# arduino_Uno_RevG-MU.net
KiCad netlist of a schematic drawn in EAGLE
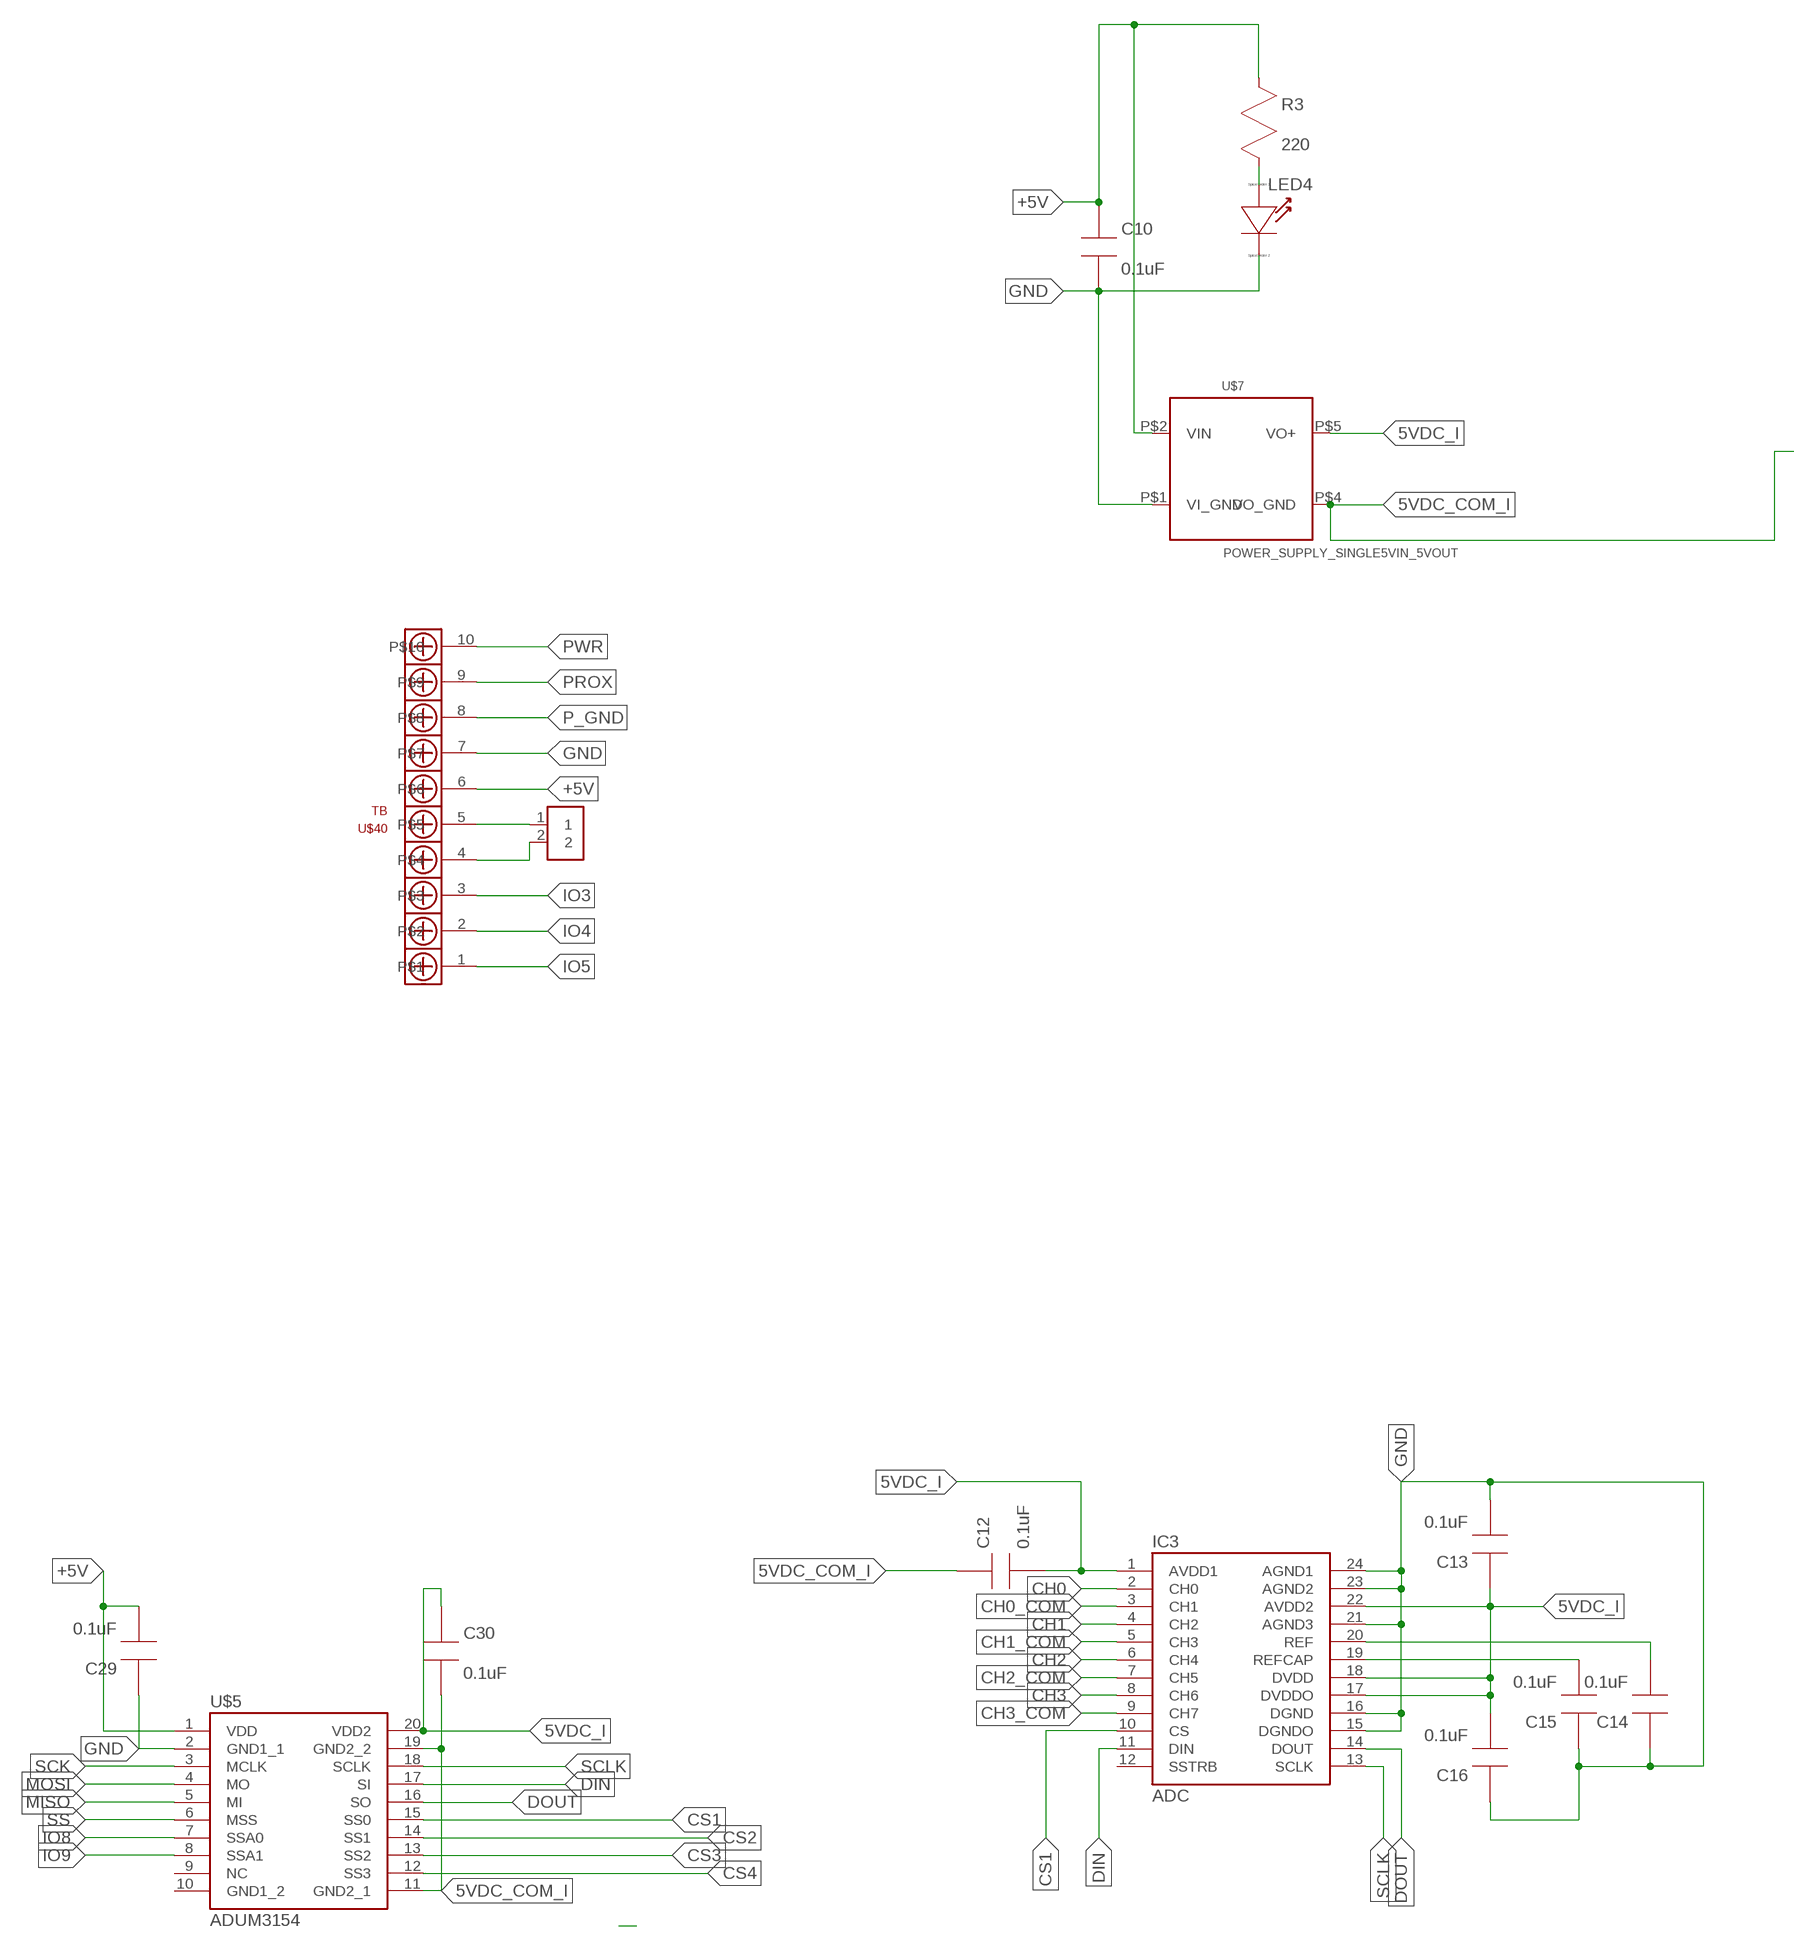
[diagram p0: schematic, sheet 1, part 1 of 2]
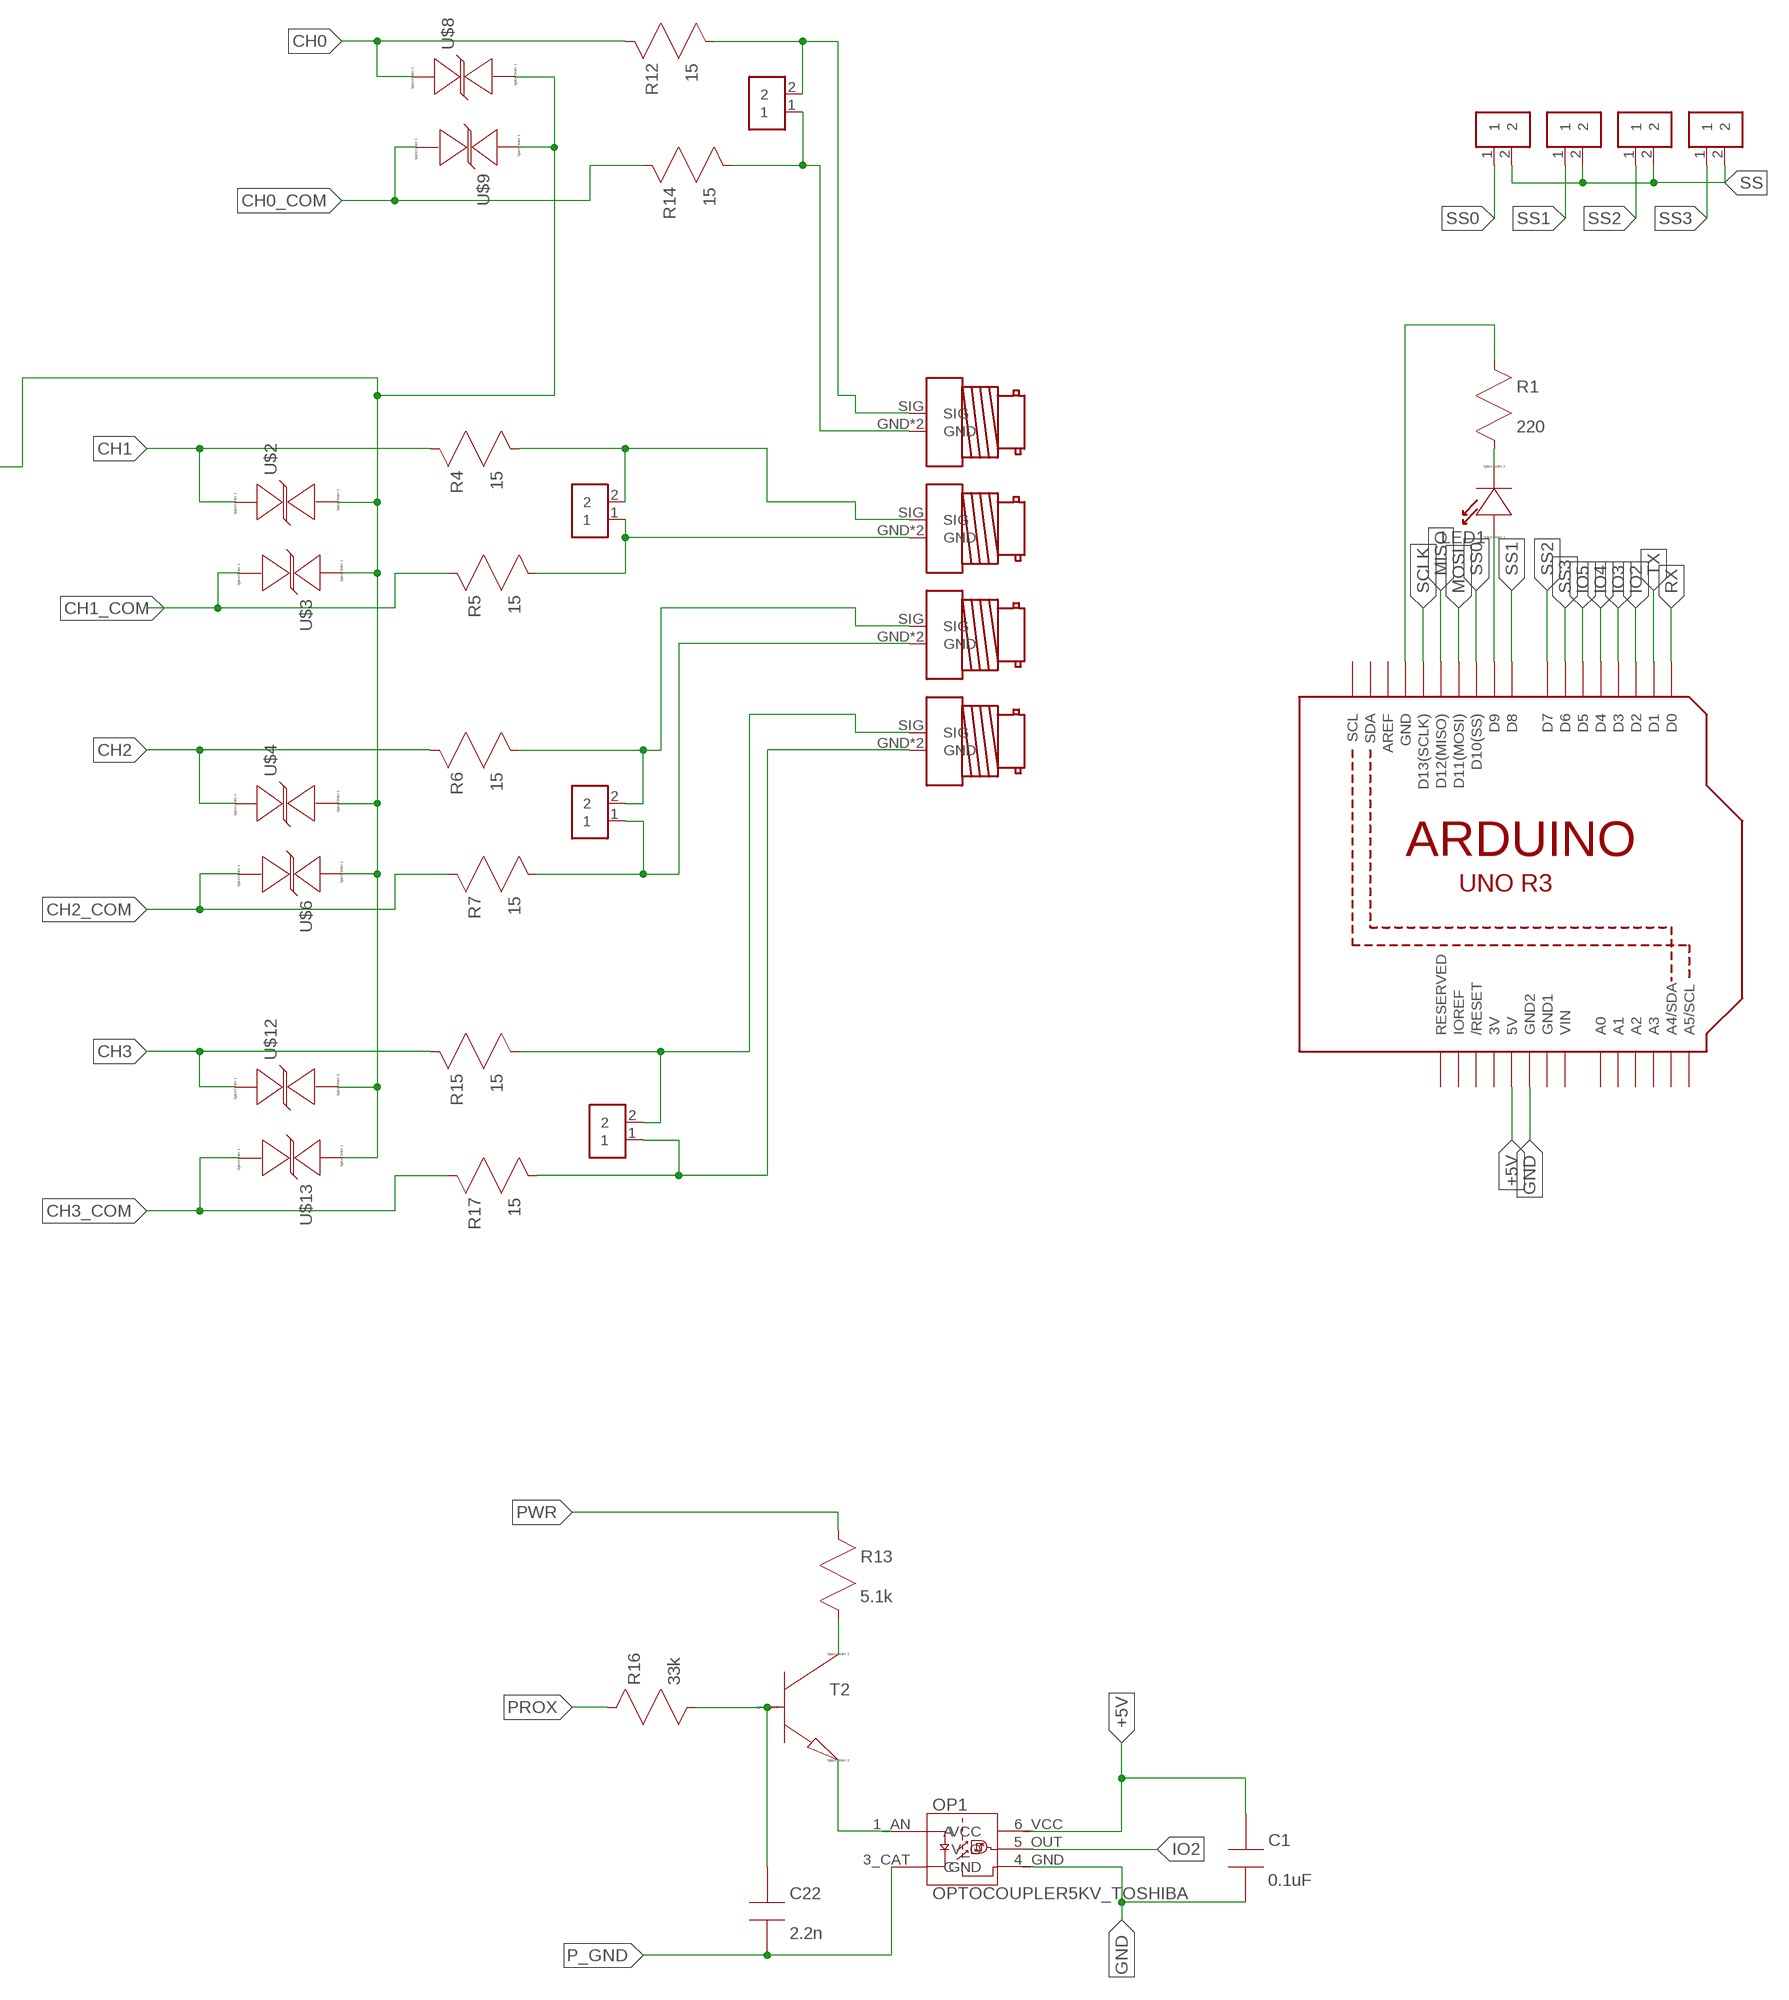
[diagram p1: schematic, sheet 1, part 2 of 2]

(export (version "E")
  (design (tool "Eeschema 10.0.6"))
  (components
    (comp (ref "C1")
      (value "0.1uF")
      (footprint "eagle-import:0805_SMD")
      (fields (field (name "MPN") "C0805C104M5UACTU"))
      (libsource (lib "eagle-import") (part "CAPACITOR0.1U_50V"))
    )
    (comp (ref "C10")
      (value "0.1uF")
      (footprint "eagle-import:0805_SMD")
      (fields (field (name "MPN") "C0805C104M5UACTU"))
      (libsource (lib "eagle-import") (part "CAPACITOR0.1U_50V"))
    )
    (comp (ref "C12")
      (value "0.1uF")
      (footprint "eagle-import:0805_SMD")
      (fields (field (name "MPN") "C0805C104M5UACTU"))
      (libsource (lib "eagle-import") (part "CAPACITOR0.1U_50V"))
    )
    (comp (ref "C13")
      (value "0.1uF")
      (footprint "eagle-import:0805_SMD")
      (fields (field (name "MPN") "C0805C104M5UACTU"))
      (libsource (lib "eagle-import") (part "CAPACITOR0.1U_50V"))
    )
    (comp (ref "C14")
      (value "0.1uF")
      (footprint "eagle-import:0805_SMD")
      (fields (field (name "MPN") "C0805C104M5UACTU"))
      (libsource (lib "eagle-import") (part "CAPACITOR0.1U_50V"))
    )
    (comp (ref "C15")
      (value "0.1uF")
      (footprint "eagle-import:0805_SMD")
      (fields (field (name "MPN") "C0805C104M5UACTU"))
      (libsource (lib "eagle-import") (part "CAPACITOR0.1U_50V"))
    )
    (comp (ref "C16")
      (value "0.1uF")
      (footprint "eagle-import:0805_SMD")
      (fields (field (name "MPN") "C0805C104M5UACTU"))
      (libsource (lib "eagle-import") (part "CAPACITOR0.1U_50V"))
    )
    (comp (ref "C22")
      (value "2.2n")
      (footprint "eagle-import:0805_SMD")
      (fields (field (name "MPN") "C0805C222K5RACTU"))
      (libsource (lib "eagle-import") (part "CAPACITOR2.2N_0805"))
    )
    (comp (ref "C29")
      (value "0.1uF")
      (footprint "eagle-import:0805_SMD")
      (fields (field (name "MPN") "C0805C104M5UACTU"))
      (libsource (lib "eagle-import") (part "CAPACITOR0.1U_50V"))
    )
    (comp (ref "C30")
      (value "0.1uF")
      (footprint "eagle-import:0805_SMD")
      (fields (field (name "MPN") "C0805C104M5UACTU"))
      (libsource (lib "eagle-import") (part "CAPACITOR0.1U_50V"))
    )
    (comp (ref "IC3")
      (value "ADC")
      (footprint "eagle-import:LS_ELECTRIC_HTSSOP24-PAD")
      (fields (field (name "MPN") "MAX1300AEUG+"))
      (libsource (lib "eagle-import") (part "ADC"))
    )
    (comp (ref "LED1")
      (value "LED0805_GREEN")
      (footprint "eagle-import:LED_0805")
      (fields (field (name "MPN") "LTST-C171GKT"))
      (libsource (lib "eagle-import") (part "LED0805_GREEN"))
    )
    (comp (ref "LED4")
      (value "LED0805_GREEN")
      (footprint "eagle-import:LED_0805")
      (fields (field (name "MPN") "LTST-C171GKT"))
      (libsource (lib "eagle-import") (part "LED0805_GREEN"))
    )
    (comp (ref "OP1")
      (value "OPTOCOUPLER5KV_TOSHIBA")
      (footprint "eagle-import:SO6L")
      (fields (field (name "MPN") "TLP2745(TP,E"))
      (libsource (lib "eagle-import") (part "OPTOCOUPLER5KV_TOSHIBA"))
    )
    (comp (ref "R1")
      (value "220")
      (footprint "eagle-import:0805_SMD")
      (fields (field (name "MPN") "RC0805FR-07220RL"))
      (libsource (lib "eagle-import") (part "RESISTOR220_0805"))
    )
    (comp (ref "R3")
      (value "220")
      (footprint "eagle-import:0805_SMD")
      (fields (field (name "MPN") "RC0805FR-07220RL"))
      (libsource (lib "eagle-import") (part "RESISTOR220_0805"))
    )
    (comp (ref "R4")
      (value "15")
      (footprint "eagle-import:0805_SMD")
      (fields (field (name "MPN") "RC0805FR-0715RL"))
      (libsource (lib "eagle-import") (part "RESISTOR15_0805"))
    )
    (comp (ref "R5")
      (value "15")
      (footprint "eagle-import:0805_SMD")
      (fields (field (name "MPN") "RC0805FR-0715RL"))
      (libsource (lib "eagle-import") (part "RESISTOR15_0805"))
    )
    (comp (ref "R6")
      (value "15")
      (footprint "eagle-import:0805_SMD")
      (fields (field (name "MPN") "RC0805FR-0715RL"))
      (libsource (lib "eagle-import") (part "RESISTOR15_0805"))
    )
    (comp (ref "R7")
      (value "15")
      (footprint "eagle-import:0805_SMD")
      (fields (field (name "MPN") "RC0805FR-0715RL"))
      (libsource (lib "eagle-import") (part "RESISTOR15_0805"))
    )
    (comp (ref "R12")
      (value "15")
      (footprint "eagle-import:0805_SMD")
      (fields (field (name "MPN") "RC0805FR-0715RL"))
      (libsource (lib "eagle-import") (part "RESISTOR15_0805"))
    )
    (comp (ref "R13")
      (value "5.1k")
      (footprint "eagle-import:0805_SMD")
      (fields (field (name "MPN") "RC0805FR-075K1L"))
      (libsource (lib "eagle-import") (part "RESISTOR5.1K_0805"))
    )
    (comp (ref "R14")
      (value "15")
      (footprint "eagle-import:0805_SMD")
      (fields (field (name "MPN") "RC0805FR-0715RL"))
      (libsource (lib "eagle-import") (part "RESISTOR15_0805"))
    )
    (comp (ref "R15")
      (value "15")
      (footprint "eagle-import:0805_SMD")
      (fields (field (name "MPN") "RC0805FR-0715RL"))
      (libsource (lib "eagle-import") (part "RESISTOR15_0805"))
    )
    (comp (ref "R16")
      (value "33k")
      (footprint "eagle-import:0805_SMD")
      (fields (field (name "MPN") "RC0805FR-0733KL"))
      (libsource (lib "eagle-import") (part "RESISTOR33K_0805"))
    )
    (comp (ref "R17")
      (value "15")
      (footprint "eagle-import:0805_SMD")
      (fields (field (name "MPN") "RC0805FR-0715RL"))
      (libsource (lib "eagle-import") (part "RESISTOR15_0805"))
    )
    (comp (ref "T2")
      (value "TRANSISTOR_NPNMMBT3904L")
      (footprint "eagle-import:SOT23")
      (fields (field (name "MPN") "MMBT3904LT1G"))
      (libsource (lib "eagle-import") (part "TRANSISTOR_NPNMMBT3904L"))
    )
    (comp (ref "U$1")
      (value "CH2")
      (footprint "eagle-import:BNC")
      (fields (field (name "MPN") "031-5431-10RFX"))
      (libsource (lib "eagle-import") (part "BNC_INVBNC_INVERT"))
    )
    (comp (ref "U$2")
      (value "TSV14VAC_18VDC")
      (footprint "eagle-import:0805_SMD")
      (fields (field (name "MPN") "VCAS08LC18A500DP"))
      (libsource (lib "eagle-import") (part "TSV14VAC_18VDC"))
    )
    (comp (ref "U$3")
      (value "TSV14VAC_18VDC")
      (footprint "eagle-import:0805_SMD")
      (fields (field (name "MPN") "VCAS08LC18A500DP"))
      (libsource (lib "eagle-import") (part "TSV14VAC_18VDC"))
    )
    (comp (ref "U$4")
      (value "TSV14VAC_18VDC")
      (footprint "eagle-import:0805_SMD")
      (fields (field (name "MPN") "VCAS08LC18A500DP"))
      (libsource (lib "eagle-import") (part "TSV14VAC_18VDC"))
    )
    (comp (ref "U$5")
      (value "ADUM3154")
      (footprint "eagle-import:SSOP_20")
      (fields (field (name "MPN") "ADUM3154ARSZ-RL7"))
      (libsource (lib "eagle-import") (part "ADUM3154"))
    )
    (comp (ref "U$6")
      (value "TSV14VAC_18VDC")
      (footprint "eagle-import:0805_SMD")
      (fields (field (name "MPN") "VCAS08LC18A500DP"))
      (libsource (lib "eagle-import") (part "TSV14VAC_18VDC"))
    )
    (comp (ref "U$7")
      (value "POWER_SUPPLY_SINGLE5VIN_5VOUT")
      (footprint "eagle-import:SMT-R1SE-0505")
      (fields (field (name "MPN") "R1SE-0505-R"))
      (libsource (lib "eagle-import") (part "POWER_SUPPLY_SINGLE5VIN_5VOUT"))
    )
    (comp (ref "U$8")
      (value "TSV14VAC_18VDC")
      (footprint "eagle-import:0805_SMD")
      (fields (field (name "MPN") "VCAS08LC18A500DP"))
      (libsource (lib "eagle-import") (part "TSV14VAC_18VDC"))
    )
    (comp (ref "U$9")
      (value "TSV14VAC_18VDC")
      (footprint "eagle-import:0805_SMD")
      (fields (field (name "MPN") "VCAS08LC18A500DP"))
      (libsource (lib "eagle-import") (part "TSV14VAC_18VDC"))
    )
    (comp (ref "U$10")
      (value "1X2_HEADER1X2")
      (footprint "eagle-import:1X2_HEADER")
      (fields (field (name "MPN") "0022032021"))
      (libsource (lib "eagle-import") (part "1X2_HEADER1X2"))
    )
    (comp (ref "U$11")
      (value "1X2_HEADER1X2")
      (footprint "eagle-import:1X2_HEADER")
      (fields (field (name "MPN") "0022032021"))
      (libsource (lib "eagle-import") (part "1X2_HEADER1X2"))
    )
    (comp (ref "U$12")
      (value "TSV14VAC_18VDC")
      (footprint "eagle-import:0805_SMD")
      (fields (field (name "MPN") "VCAS08LC18A500DP"))
      (libsource (lib "eagle-import") (part "TSV14VAC_18VDC"))
    )
    (comp (ref "U$13")
      (value "TSV14VAC_18VDC")
      (footprint "eagle-import:0805_SMD")
      (fields (field (name "MPN") "VCAS08LC18A500DP"))
      (libsource (lib "eagle-import") (part "TSV14VAC_18VDC"))
    )
    (comp (ref "U$14")
      (value "1X2_HEADER1X2")
      (footprint "eagle-import:1X2_HEADER")
      (fields (field (name "MPN") "0022032021"))
      (libsource (lib "eagle-import") (part "1X2_HEADER1X2"))
    )
    (comp (ref "U$15")
      (value "1X2_HEADER1X2")
      (footprint "eagle-import:1X2_HEADER")
      (fields (field (name "MPN") "0022032021"))
      (libsource (lib "eagle-import") (part "1X2_HEADER1X2"))
    )
    (comp (ref "U$16")
      (value "1X2_HEADER1X2")
      (footprint "eagle-import:1X2_HEADER")
      (fields (field (name "MPN") "0022032021"))
      (libsource (lib "eagle-import") (part "1X2_HEADER1X2"))
    )
    (comp (ref "U$17")
      (value "1X2_HEADER1X2")
      (footprint "eagle-import:1X2_HEADER")
      (fields (field (name "MPN") "0022032021"))
      (libsource (lib "eagle-import") (part "1X2_HEADER1X2"))
    )
    (comp (ref "U$18")
      (value "1X2_HEADER1X2")
      (footprint "eagle-import:1X2_HEADER")
      (fields (field (name "MPN") "0022032021"))
      (libsource (lib "eagle-import") (part "1X2_HEADER1X2"))
    )
    (comp (ref "U$19")
      (value "1X2_HEADER1X2")
      (footprint "eagle-import:1X2_HEADER")
      (fields (field (name "MPN") "0022032021"))
      (libsource (lib "eagle-import") (part "1X2_HEADER1X2"))
    )
    (comp (ref "U$20")
      (value "1X2_HEADER1X2")
      (footprint "eagle-import:1X2_HEADER")
      (fields (field (name "MPN") "0022032021"))
      (libsource (lib "eagle-import") (part "1X2_HEADER1X2"))
    )
    (comp (ref "U$34")
      (value "CH1")
      (footprint "eagle-import:BNC")
      (fields (field (name "MPN") "031-5431-10RFX"))
      (libsource (lib "eagle-import") (part "BNC_INVBNC_INVERT"))
    )
    (comp (ref "U$35")
      (value "CH3")
      (footprint "eagle-import:BNC")
      (fields (field (name "MPN") "031-5431-10RFX"))
      (libsource (lib "eagle-import") (part "BNC_INVBNC_INVERT"))
    )
    (comp (ref "U$36")
      (value "CG4")
      (footprint "eagle-import:BNC")
      (fields (field (name "MPN") "031-5431-10RFX"))
      (libsource (lib "eagle-import") (part "BNC_INVBNC_INVERT"))
    )
    (comp (ref "U$40")
      (value "TB")
      (footprint "eagle-import:TB_10P")
      (libsource (lib "eagle-import") (part "TERMINAL_BLOCK_10PHOENIX_10"))
    )
    (comp (ref "U4")
      (value "ARDUINOR3-DIMENSION")
      (footprint "eagle-import:ARDUINOR3")
      (libsource (lib "eagle-import") (part "ARDUINOR3-DIMENSION"))
    )
  )
  (nets
    (net (code "1") (name "+5V") (class "Default")
      (node (ref "C1") (pin "1") (pinfunction "A_1") (pintype "passive"))
      (node (ref "C10") (pin "1") (pinfunction "A_1") (pintype "passive"))
      (node (ref "C29") (pin "2") (pinfunction "B_2") (pintype "passive"))
      (node (ref "OP1") (pin "6_VCC") (pinfunction "VCC_6_VCC") (pintype "bidirectional"))
      (node (ref "R3") (pin "1") (pinfunction "A_1") (pintype "passive"))
      (node (ref "U$40") (pin "6") (pinfunction "P$6_6") (pintype "bidirectional"))
      (node (ref "U$5") (pin "1") (pinfunction "VDD_1") (pintype "power_in"))
      (node (ref "U$7") (pin "P$2") (pinfunction "VIN_P$2") (pintype "bidirectional"))
      (node (ref "U4") (pin "5V") (pinfunction "5V_5V") (pintype "power_in"))
    )
    (net (code "2") (name "/3V") (class "Default")
      (node (ref "U4") (pin "3V") (pinfunction "3V_3V") (pintype "power_in"))
    )
    (net (code "3") (name "/GND1") (class "Default")
      (node (ref "U4") (pin "GND1") (pinfunction "GND1_GND1") (pintype "power_in"))
    )
    (net (code "4") (name "/SSTRB") (class "Default")
      (node (ref "IC3") (pin "12") (pinfunction "SSTRB_12") (pintype "power_in"))
    )
    (net (code "5") (name "/VIN") (class "Default")
      (node (ref "U4") (pin "VIN") (pinfunction "VIN_VIN") (pintype "power_in"))
    )
    (net (code "6") (name "5VDC_COM_I") (class "Default")
      (node (ref "C12") (pin "1") (pinfunction "A_1") (pintype "passive"))
      (node (ref "C30") (pin "2") (pinfunction "B_2") (pintype "passive"))
      (node (ref "U$12") (pin "2") (pinfunction "GND_2") (pintype "passive"))
      (node (ref "U$13") (pin "1") (pinfunction "+_1") (pintype "passive"))
      (node (ref "U$2") (pin "2") (pinfunction "GND_2") (pintype "passive"))
      (node (ref "U$3") (pin "1") (pinfunction "+_1") (pintype "passive"))
      (node (ref "U$4") (pin "2") (pinfunction "GND_2") (pintype "passive"))
      (node (ref "U$5") (pin "11") (pinfunction "GND2_1_11") (pintype "bidirectional"))
      (node (ref "U$5") (pin "19") (pinfunction "GND2_2_19") (pintype "bidirectional"))
      (node (ref "U$6") (pin "1") (pinfunction "+_1") (pintype "passive"))
      (node (ref "U$7") (pin "P$4") (pinfunction "VO_GND_P$4") (pintype "bidirectional"))
      (node (ref "U$8") (pin "2") (pinfunction "GND_2") (pintype "passive"))
      (node (ref "U$9") (pin "1") (pinfunction "+_1") (pintype "passive"))
    )
    (net (code "7") (name "5VDC_I") (class "Default")
      (node (ref "C12") (pin "2") (pinfunction "B_2") (pintype "passive"))
      (node (ref "C13") (pin "1") (pinfunction "A_1") (pintype "passive"))
      (node (ref "C16") (pin "2") (pinfunction "B_2") (pintype "passive"))
      (node (ref "C30") (pin "1") (pinfunction "A_1") (pintype "passive"))
      (node (ref "IC3") (pin "1") (pinfunction "AVDD1_1") (pintype "power_in"))
      (node (ref "IC3") (pin "17") (pinfunction "DVDDO_17") (pintype "bidirectional"))
      (node (ref "IC3") (pin "18") (pinfunction "DVDD_18") (pintype "bidirectional"))
      (node (ref "IC3") (pin "22") (pinfunction "AVDD2_22") (pintype "bidirectional"))
      (node (ref "U$5") (pin "20") (pinfunction "VDD2_20") (pintype "bidirectional"))
      (node (ref "U$7") (pin "P$5") (pinfunction "VO+_P$5") (pintype "bidirectional"))
    )
    (net (code "8") (name "CH0") (class "Default")
      (node (ref "IC3") (pin "2") (pinfunction "CH0_2") (pintype "power_in"))
      (node (ref "R12") (pin "1") (pinfunction "A_1") (pintype "passive"))
      (node (ref "U$8") (pin "1") (pinfunction "+_1") (pintype "passive"))
    )
    (net (code "9") (name "CH0_COM") (class "Default")
      (node (ref "IC3") (pin "3") (pinfunction "CH1_3") (pintype "bidirectional"))
      (node (ref "R14") (pin "1") (pinfunction "A_1") (pintype "passive"))
      (node (ref "U$9") (pin "2") (pinfunction "GND_2") (pintype "passive"))
    )
    (net (code "10") (name "CH1") (class "Default")
      (node (ref "IC3") (pin "4") (pinfunction "CH2_4") (pintype "power_in"))
      (node (ref "R4") (pin "1") (pinfunction "A_1") (pintype "passive"))
      (node (ref "U$2") (pin "1") (pinfunction "+_1") (pintype "passive"))
    )
    (net (code "11") (name "CH1_COM") (class "Default")
      (node (ref "IC3") (pin "5") (pinfunction "CH3_5") (pintype "bidirectional"))
      (node (ref "R5") (pin "1") (pinfunction "A_1") (pintype "passive"))
      (node (ref "U$3") (pin "2") (pinfunction "GND_2") (pintype "passive"))
    )
    (net (code "12") (name "CH2") (class "Default")
      (node (ref "IC3") (pin "6") (pinfunction "CH4_6") (pintype "bidirectional"))
      (node (ref "R6") (pin "1") (pinfunction "A_1") (pintype "passive"))
      (node (ref "U$4") (pin "1") (pinfunction "+_1") (pintype "passive"))
    )
    (net (code "13") (name "CH2_COM") (class "Default")
      (node (ref "IC3") (pin "7") (pinfunction "CH5_7") (pintype "bidirectional"))
      (node (ref "R7") (pin "1") (pinfunction "A_1") (pintype "passive"))
      (node (ref "U$6") (pin "2") (pinfunction "GND_2") (pintype "passive"))
    )
    (net (code "14") (name "CH3") (class "Default")
      (node (ref "IC3") (pin "8") (pinfunction "CH6_8") (pintype "bidirectional"))
      (node (ref "R15") (pin "1") (pinfunction "A_1") (pintype "passive"))
      (node (ref "U$12") (pin "1") (pinfunction "+_1") (pintype "passive"))
    )
    (net (code "15") (name "CH3_COM") (class "Default")
      (node (ref "IC3") (pin "9") (pinfunction "CH7_9") (pintype "bidirectional"))
      (node (ref "R17") (pin "1") (pinfunction "A_1") (pintype "passive"))
      (node (ref "U$13") (pin "2") (pinfunction "GND_2") (pintype "passive"))
    )
    (net (code "16") (name "CS1") (class "Default")
      (node (ref "IC3") (pin "10") (pinfunction "CS_10") (pintype "bidirectional"))
      (node (ref "U$5") (pin "15") (pinfunction "SS0_15") (pintype "bidirectional"))
    )
    (net (code "17") (name "CS2") (class "Default")
      (node (ref "U$5") (pin "14") (pinfunction "SS1_14") (pintype "bidirectional"))
    )
    (net (code "18") (name "CS3") (class "Default")
      (node (ref "U$5") (pin "13") (pinfunction "SS2_13") (pintype "bidirectional"))
    )
    (net (code "19") (name "CS4") (class "Default")
      (node (ref "U$5") (pin "12") (pinfunction "SS3_12") (pintype "bidirectional"))
    )
    (net (code "20") (name "DIN") (class "Default")
      (node (ref "IC3") (pin "11") (pinfunction "DIN_11") (pintype "power_in"))
      (node (ref "U$5") (pin "17") (pinfunction "SI_17") (pintype "bidirectional"))
    )
    (net (code "21") (name "DOUT") (class "Default")
      (node (ref "IC3") (pin "14") (pinfunction "DOUT_14") (pintype "bidirectional"))
      (node (ref "U$5") (pin "16") (pinfunction "SO_16") (pintype "bidirectional"))
    )
    (net (code "22") (name "GND") (class "Default")
      (node (ref "C1") (pin "2") (pinfunction "B_2") (pintype "passive"))
      (node (ref "C10") (pin "2") (pinfunction "B_2") (pintype "passive"))
      (node (ref "C13") (pin "2") (pinfunction "B_2") (pintype "passive"))
      (node (ref "C14") (pin "1") (pinfunction "A_1") (pintype "passive"))
      (node (ref "C15") (pin "1") (pinfunction "A_1") (pintype "passive"))
      (node (ref "C16") (pin "1") (pinfunction "A_1") (pintype "passive"))
      (node (ref "C29") (pin "1") (pinfunction "A_1") (pintype "passive"))
      (node (ref "IC3") (pin "15") (pinfunction "DGNDO_15") (pintype "bidirectional"))
      (node (ref "IC3") (pin "16") (pinfunction "DGND_16") (pintype "bidirectional"))
      (node (ref "IC3") (pin "21") (pinfunction "AGND3_21") (pintype "bidirectional"))
      (node (ref "IC3") (pin "23") (pinfunction "AGND2_23") (pintype "bidirectional"))
      (node (ref "IC3") (pin "24") (pinfunction "AGND1_24") (pintype "power_in"))
      (node (ref "LED4") (pin "C") (pinfunction "-_C") (pintype "passive"))
      (node (ref "OP1") (pin "4_GND") (pinfunction "GND_4_GND") (pintype "bidirectional"))
      (node (ref "R1") (pin "1") (pinfunction "A_1") (pintype "passive"))
      (node (ref "U$40") (pin "7") (pinfunction "P$7_7") (pintype "bidirectional"))
      (node (ref "U$5") (pin "2") (pinfunction "GND1_1_2") (pintype "input"))
      (node (ref "U$7") (pin "P$1") (pinfunction "VI_GND_P$1") (pintype "bidirectional"))
      (node (ref "U4") (pin "GND") (pinfunction "GND_GND") (pintype "power_in"))
      (node (ref "U4") (pin "GND2") (pinfunction "GND2_GND2") (pintype "power_in"))
    )
    (net (code "23") (name "IO2") (class "Default")
      (node (ref "OP1") (pin "5_OUT") (pinfunction "V_O_5_OUT") (pintype "bidirectional"))
      (node (ref "U4") (pin "D2") (pinfunction "D2_D2") (pintype "bidirectional"))
    )
    (net (code "24") (name "IO3") (class "Default")
      (node (ref "U$40") (pin "3") (pinfunction "P$3_3") (pintype "bidirectional"))
      (node (ref "U4") (pin "D3") (pinfunction "D3_D3") (pintype "bidirectional"))
    )
    (net (code "25") (name "IO4") (class "Default")
      (node (ref "U$40") (pin "2") (pinfunction "P$2_2") (pintype "bidirectional"))
      (node (ref "U4") (pin "D4") (pinfunction "D4_D4") (pintype "bidirectional"))
    )
    (net (code "26") (name "IO5") (class "Default")
      (node (ref "U$40") (pin "1") (pinfunction "P$1_1") (pintype "bidirectional"))
      (node (ref "U4") (pin "D5") (pinfunction "D5_D5") (pintype "bidirectional"))
    )
    (net (code "27") (name "IO8") (class "Default")
      (node (ref "U$5") (pin "7") (pinfunction "SSA0_7") (pintype "bidirectional"))
    )
    (net (code "28") (name "IO9") (class "Default")
      (node (ref "U$5") (pin "8") (pinfunction "SSA1_8") (pintype "bidirectional"))
    )
    (net (code "29") (name "MISO") (class "Default")
      (node (ref "U$5") (pin "5") (pinfunction "MI_5") (pintype "bidirectional"))
      (node (ref "U4") (pin "D12") (pinfunction "D12(MISO)_D12") (pintype "bidirectional"))
    )
    (net (code "30") (name "MOSI") (class "Default")
      (node (ref "U$5") (pin "4") (pinfunction "MO_4") (pintype "input"))
      (node (ref "U4") (pin "D11") (pinfunction "D11(MOSI)_D11") (pintype "bidirectional"))
    )
    (net (code "31") (name "Net-(C14-B)") (class "Default")
      (node (ref "C14") (pin "2") (pinfunction "B_2") (pintype "passive"))
      (node (ref "IC3") (pin "20") (pinfunction "REF_20") (pintype "bidirectional"))
    )
    (net (code "32") (name "Net-(C15-B)") (class "Default")
      (node (ref "C15") (pin "2") (pinfunction "B_2") (pintype "passive"))
      (node (ref "IC3") (pin "19") (pinfunction "REFCAP_19") (pintype "bidirectional"))
    )
    (net (code "33") (name "Net-(C22-A)") (class "Default")
      (node (ref "C22") (pin "1") (pinfunction "A_1") (pintype "passive"))
      (node (ref "R16") (pin "2") (pinfunction "B_2") (pintype "passive"))
      (node (ref "T2") (pin "1") (pinfunction "B_1") (pintype "passive"))
    )
    (net (code "34") (name "Net-(LED1-+)") (class "Default")
      (node (ref "LED1") (pin "A") (pinfunction "+_A") (pintype "passive"))
      (node (ref "U4") (pin "D9") (pinfunction "D9_D9") (pintype "bidirectional"))
    )
    (net (code "35") (name "Net-(LED1--)") (class "Default")
      (node (ref "LED1") (pin "C") (pinfunction "-_C") (pintype "passive"))
      (node (ref "R1") (pin "2") (pinfunction "B_2") (pintype "passive"))
    )
    (net (code "36") (name "Net-(LED4-+)") (class "Default")
      (node (ref "LED4") (pin "A") (pinfunction "+_A") (pintype "passive"))
      (node (ref "R3") (pin "2") (pinfunction "B_2") (pintype "passive"))
    )
    (net (code "37") (name "Net-(OP1-A)") (class "Default")
      (node (ref "OP1") (pin "1_AN") (pinfunction "A_1_AN") (pintype "bidirectional"))
      (node (ref "T2") (pin "2") (pinfunction "E_2") (pintype "passive"))
    )
    (net (code "38") (name "Net-(R4-B)") (class "Default")
      (node (ref "R4") (pin "2") (pinfunction "B_2") (pintype "passive"))
      (node (ref "U$1") (pin "SIG") (pinfunction "SIG_SIG") (pintype "bidirectional"))
      (node (ref "U$11") (pin "2") (pinfunction "2_2") (pintype "bidirectional"))
    )
    (net (code "39") (name "Net-(R5-B)") (class "Default")
      (node (ref "R5") (pin "2") (pinfunction "B_2") (pintype "passive"))
      (node (ref "U$1") (pin "GND") (pinfunction "GND_GND") (pintype "bidirectional"))
      (node (ref "U$1") (pin "GND_INV") (pinfunction "GND_GND_INV") (pintype "bidirectional"))
      (node (ref "U$11") (pin "1") (pinfunction "1_1") (pintype "bidirectional"))
    )
    (net (code "40") (name "Net-(R6-B)") (class "Default")
      (node (ref "R6") (pin "2") (pinfunction "B_2") (pintype "passive"))
      (node (ref "U$18") (pin "2") (pinfunction "2_2") (pintype "bidirectional"))
      (node (ref "U$35") (pin "SIG") (pinfunction "SIG_SIG") (pintype "bidirectional"))
    )
    (net (code "41") (name "Net-(R7-B)") (class "Default")
      (node (ref "R7") (pin "2") (pinfunction "B_2") (pintype "passive"))
      (node (ref "U$18") (pin "1") (pinfunction "1_1") (pintype "bidirectional"))
      (node (ref "U$35") (pin "GND") (pinfunction "GND_GND") (pintype "bidirectional"))
      (node (ref "U$35") (pin "GND_INV") (pinfunction "GND_GND_INV") (pintype "bidirectional"))
    )
    (net (code "42") (name "Net-(R12-B)") (class "Default")
      (node (ref "R12") (pin "2") (pinfunction "B_2") (pintype "passive"))
      (node (ref "U$10") (pin "2") (pinfunction "2_2") (pintype "bidirectional"))
      (node (ref "U$34") (pin "SIG") (pinfunction "SIG_SIG") (pintype "bidirectional"))
    )
    (net (code "43") (name "Net-(R13-B)") (class "Default")
      (node (ref "R13") (pin "2") (pinfunction "B_2") (pintype "passive"))
      (node (ref "T2") (pin "3") (pinfunction "C_3") (pintype "passive"))
    )
    (net (code "44") (name "Net-(R14-B)") (class "Default")
      (node (ref "R14") (pin "2") (pinfunction "B_2") (pintype "passive"))
      (node (ref "U$10") (pin "1") (pinfunction "1_1") (pintype "bidirectional"))
      (node (ref "U$34") (pin "GND") (pinfunction "GND_GND") (pintype "bidirectional"))
      (node (ref "U$34") (pin "GND_INV") (pinfunction "GND_GND_INV") (pintype "bidirectional"))
    )
    (net (code "45") (name "Net-(R15-B)") (class "Default")
      (node (ref "R15") (pin "2") (pinfunction "B_2") (pintype "passive"))
      (node (ref "U$19") (pin "2") (pinfunction "2_2") (pintype "bidirectional"))
      (node (ref "U$36") (pin "SIG") (pinfunction "SIG_SIG") (pintype "bidirectional"))
    )
    (net (code "46") (name "Net-(R17-B)") (class "Default")
      (node (ref "R17") (pin "2") (pinfunction "B_2") (pintype "passive"))
      (node (ref "U$19") (pin "1") (pinfunction "1_1") (pintype "bidirectional"))
      (node (ref "U$36") (pin "GND") (pinfunction "GND_GND") (pintype "bidirectional"))
      (node (ref "U$36") (pin "GND_INV") (pinfunction "GND_GND_INV") (pintype "bidirectional"))
    )
    (net (code "47") (name "Net-(U$40-P$4)") (class "Default")
      (node (ref "U$20") (pin "2") (pinfunction "2_2") (pintype "bidirectional"))
      (node (ref "U$40") (pin "4") (pinfunction "P$4_4") (pintype "bidirectional"))
    )
    (net (code "48") (name "Net-(U$40-P$5)") (class "Default")
      (node (ref "U$20") (pin "1") (pinfunction "1_1") (pintype "bidirectional"))
      (node (ref "U$40") (pin "5") (pinfunction "P$5_5") (pintype "bidirectional"))
    )
    (net (code "49") (name "PROX") (class "Default")
      (node (ref "R16") (pin "1") (pinfunction "A_1") (pintype "passive"))
      (node (ref "U$40") (pin "9") (pinfunction "P$9_9") (pintype "bidirectional"))
    )
    (net (code "50") (name "PWR") (class "Default")
      (node (ref "R13") (pin "1") (pinfunction "A_1") (pintype "passive"))
      (node (ref "U$40") (pin "10") (pinfunction "P$10_10") (pintype "bidirectional"))
    )
    (net (code "51") (name "P_GND") (class "Default")
      (node (ref "C22") (pin "2") (pinfunction "B_2") (pintype "passive"))
      (node (ref "OP1") (pin "3_CAT") (pinfunction "C_3_CAT") (pintype "bidirectional"))
      (node (ref "U$40") (pin "8") (pinfunction "P$8_8") (pintype "bidirectional"))
    )
    (net (code "52") (name "RX") (class "Default")
      (node (ref "U4") (pin "D0") (pinfunction "D0_D0") (pintype "bidirectional"))
    )
    (net (code "53") (name "SCK") (class "Default")
      (node (ref "U$5") (pin "3") (pinfunction "MCLK_3") (pintype "output"))
    )
    (net (code "54") (name "SCLK") (class "Default")
      (node (ref "IC3") (pin "13") (pinfunction "SCLK_13") (pintype "bidirectional"))
      (node (ref "U$5") (pin "18") (pinfunction "SCLK_18") (pintype "bidirectional"))
      (node (ref "U4") (pin "D13") (pinfunction "D13(SCLK)_D13") (pintype "bidirectional"))
    )
    (net (code "55") (name "SS") (class "Default")
      (node (ref "U$14") (pin "2") (pinfunction "2_2") (pintype "bidirectional"))
      (node (ref "U$15") (pin "2") (pinfunction "2_2") (pintype "bidirectional"))
      (node (ref "U$16") (pin "2") (pinfunction "2_2") (pintype "bidirectional"))
      (node (ref "U$17") (pin "2") (pinfunction "2_2") (pintype "bidirectional"))
      (node (ref "U$5") (pin "6") (pinfunction "MSS_6") (pintype "bidirectional"))
    )
    (net (code "56") (name "SS0") (class "Default")
      (node (ref "U$14") (pin "1") (pinfunction "1_1") (pintype "bidirectional"))
      (node (ref "U4") (pin "D10") (pinfunction "D10(SS)_D10") (pintype "bidirectional"))
    )
    (net (code "57") (name "SS1") (class "Default")
      (node (ref "U$15") (pin "1") (pinfunction "1_1") (pintype "bidirectional"))
      (node (ref "U4") (pin "D8") (pinfunction "D8_D8") (pintype "bidirectional"))
    )
    (net (code "58") (name "SS2") (class "Default")
      (node (ref "U$16") (pin "1") (pinfunction "1_1") (pintype "bidirectional"))
      (node (ref "U4") (pin "D7") (pinfunction "D7_D7") (pintype "bidirectional"))
    )
    (net (code "59") (name "SS3") (class "Default")
      (node (ref "U$17") (pin "1") (pinfunction "1_1") (pintype "bidirectional"))
      (node (ref "U4") (pin "D6") (pinfunction "D6_D6") (pintype "bidirectional"))
    )
    (net (code "60") (name "TX") (class "Default")
      (node (ref "U4") (pin "D1") (pinfunction "D1_D1") (pintype "bidirectional"))
    )
    (net (code "61") (name "unconnected-(U$5-GND1_2-Pad10)") (class "Default")
      (node (ref "U$5") (pin "10") (pinfunction "GND1_2_10") (pintype "bidirectional"))
    )
    (net (code "62") (name "unconnected-(U$5-NC-Pad9)") (class "Default")
      (node (ref "U$5") (pin "9") (pinfunction "NC_9") (pintype "bidirectional"))
    )
    (net (code "63") (name "unconnected-(U4-A4{slash}SDA-PadA4)") (class "Default")
      (node (ref "U4") (pin "A4") (pinfunction "A4/SDA_A4") (pintype "bidirectional"))
    )
    (net (code "64") (name "unconnected-(U4-A5{slash}SCL-PadA5)") (class "Default")
      (node (ref "U4") (pin "A5") (pinfunction "A5/SCL_A5") (pintype "bidirectional"))
    )
    (net (code "65") (name "unconnected-(U4-PadA0)") (class "Default")
      (node (ref "U4") (pin "A0") (pinfunction "A0_A0") (pintype "bidirectional"))
    )
    (net (code "66") (name "unconnected-(U4-PadA1)") (class "Default")
      (node (ref "U4") (pin "A1") (pinfunction "A1_A1") (pintype "bidirectional"))
    )
    (net (code "67") (name "unconnected-(U4-PadA2)") (class "Default")
      (node (ref "U4") (pin "A2") (pinfunction "A2_A2") (pintype "bidirectional"))
    )
    (net (code "68") (name "unconnected-(U4-PadA3)") (class "Default")
      (node (ref "U4") (pin "A3") (pinfunction "A3_A3") (pintype "bidirectional"))
    )
    (net (code "69") (name "unconnected-(U4-PadAREF)") (class "Default")
      (node (ref "U4") (pin "AREF") (pinfunction "AREF_AREF") (pintype "bidirectional"))
    )
    (net (code "70") (name "unconnected-(U4-PadIOREF)") (class "Default")
      (node (ref "U4") (pin "IOREF") (pinfunction "IOREF_IOREF") (pintype "output"))
    )
    (net (code "71") (name "unconnected-(U4-PadRESERVED)") (class "Default")
      (node (ref "U4") (pin "RESERVED") (pinfunction "RESERVED_RESERVED") (pintype "no_connect"))
    )
    (net (code "72") (name "unconnected-(U4-PadSCL)") (class "Default")
      (node (ref "U4") (pin "SCL") (pinfunction "SCL_SCL") (pintype "bidirectional"))
    )
    (net (code "73") (name "unconnected-(U4-PadSDA)") (class "Default")
      (node (ref "U4") (pin "SDA") (pinfunction "SDA_SDA") (pintype "bidirectional"))
    )
    (net (code "74") (name "unconnected-(U4-{slash}RESET-PadRESET)") (class "Default")
      (node (ref "U4") (pin "RESET") (pinfunction "/RESET_RESET") (pintype "bidirectional"))
    )
  )
)
